# ThoraxSensor3_0.net
KiCad netlist of a schematic drawn in EAGLE
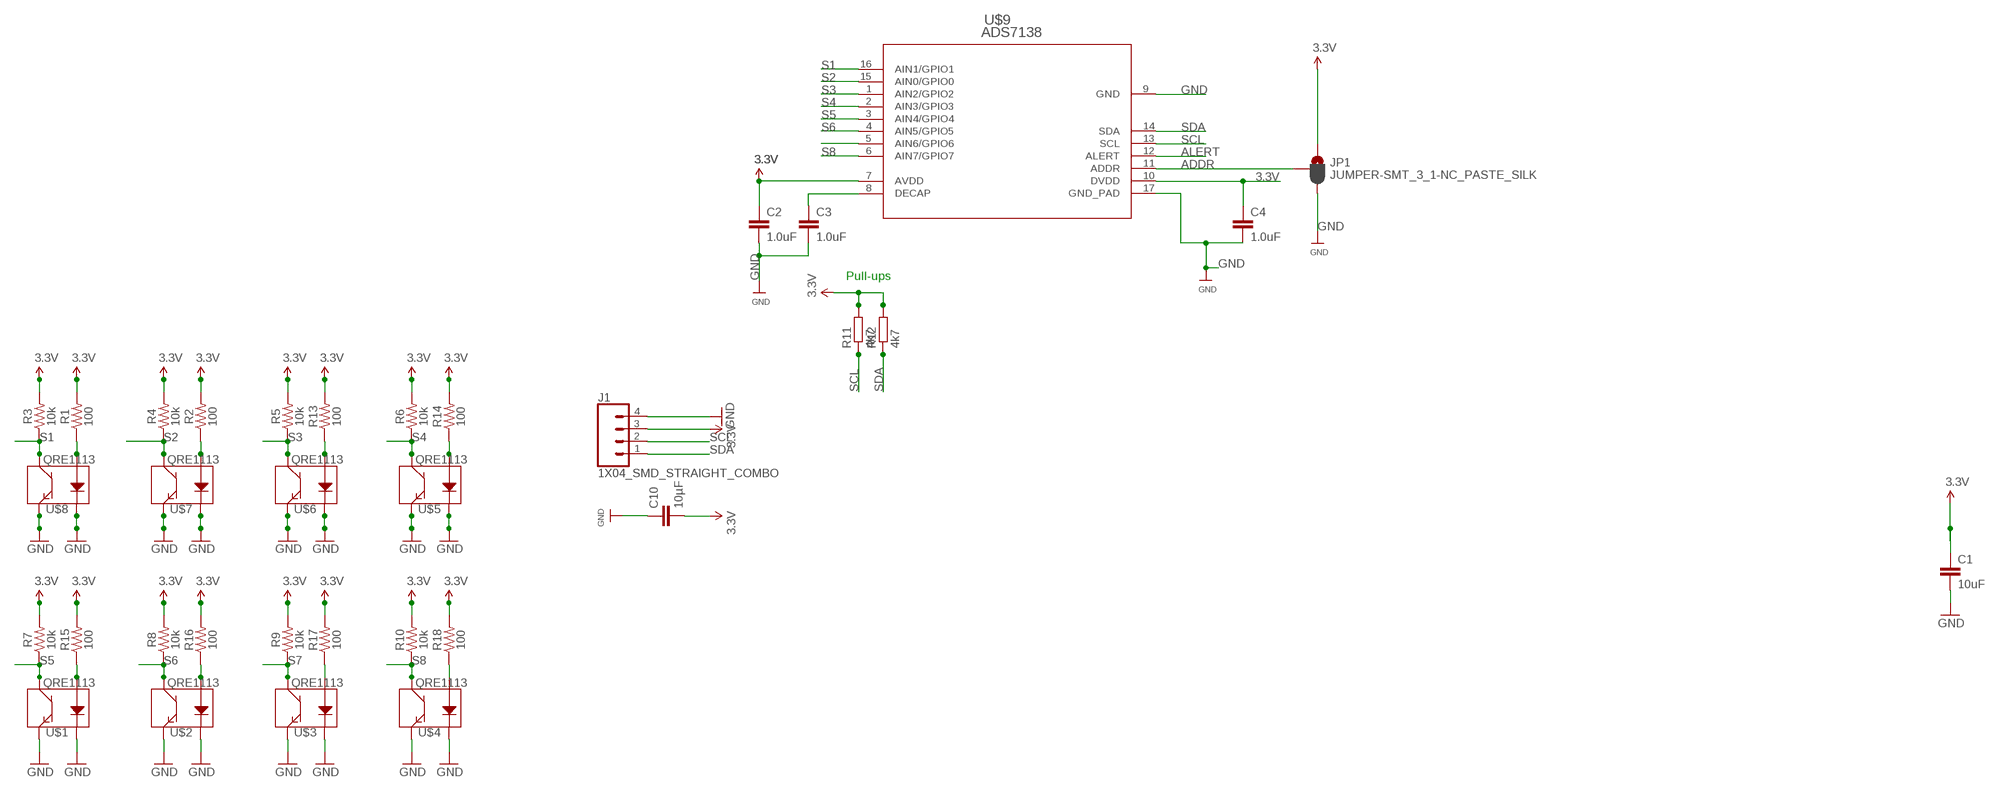
[diagram p0: schematic, sheet 1]

(export (version "E")
  (design (tool "Eeschema 10.0.6"))
  (components
    (comp (ref "C1")
      (value "10uF")
      (footprint "eagle-import:0805")
      (libsource (lib "eagle-import") (part "10UF-0805-10V-10%"))
    )
    (comp (ref "C2")
      (value "1.0uF")
      (footprint "eagle-import:0603")
      (libsource (lib "eagle-import") (part "1.0UF-0603-16V-10%"))
    )
    (comp (ref "C3")
      (value "1.0uF")
      (footprint "eagle-import:0603")
      (libsource (lib "eagle-import") (part "1.0UF-0603-16V-10%"))
    )
    (comp (ref "C4")
      (value "1.0uF")
      (footprint "eagle-import:0603")
      (libsource (lib "eagle-import") (part "1.0UF-0603-16V-10%"))
    )
    (comp (ref "C10")
      (value "10µF")
      (footprint "eagle-import:C0805")
      (libsource (lib "eagle-import") (part "C-EUC0805"))
    )
    (comp (ref "J1")
      (value "1X04_SMD_STRAIGHT_COMBO")
      (footprint "eagle-import:1X04_SMD_VERTICAL_COMBO")
      (libsource (lib "eagle-import") (part "CONN_04SMD_STRAIGHT_COMBO"))
    )
    (comp (ref "JP1")
      (value "JUMPER-SMT_3_1-NC_PASTE_SILK")
      (footprint "eagle-import:SMT-JUMPER_3_1-NC_PASTE_SILK")
      (libsource (lib "eagle-import") (part "JUMPER-SMT_3_1-NC_PASTE_SILK"))
    )
    (comp (ref "R1")
      (value "100")
      (footprint "eagle-import:0603")
      (libsource (lib "eagle-import") (part "100OHM-0603-1/4W-5%"))
    )
    (comp (ref "R2")
      (value "100")
      (footprint "eagle-import:0603")
      (libsource (lib "eagle-import") (part "100OHM-0603-1/4W-5%"))
    )
    (comp (ref "R3")
      (value "10k")
      (footprint "eagle-import:0603")
      (libsource (lib "eagle-import") (part "10KOHM-0603-1/10W-1%"))
    )
    (comp (ref "R4")
      (value "10k")
      (footprint "eagle-import:0603")
      (libsource (lib "eagle-import") (part "10KOHM-0603-1/10W-1%"))
    )
    (comp (ref "R5")
      (value "10k")
      (footprint "eagle-import:0603")
      (libsource (lib "eagle-import") (part "10KOHM-0603-1/10W-1%"))
    )
    (comp (ref "R6")
      (value "10k")
      (footprint "eagle-import:0603")
      (libsource (lib "eagle-import") (part "10KOHM-0603-1/10W-1%"))
    )
    (comp (ref "R7")
      (value "10k")
      (footprint "eagle-import:0603")
      (libsource (lib "eagle-import") (part "10KOHM-0603-1/10W-1%"))
    )
    (comp (ref "R8")
      (value "10k")
      (footprint "eagle-import:0603")
      (libsource (lib "eagle-import") (part "10KOHM-0603-1/10W-1%"))
    )
    (comp (ref "R9")
      (value "10k")
      (footprint "eagle-import:0603")
      (libsource (lib "eagle-import") (part "10KOHM-0603-1/10W-1%"))
    )
    (comp (ref "R10")
      (value "10k")
      (footprint "eagle-import:0603")
      (libsource (lib "eagle-import") (part "10KOHM-0603-1/10W-1%"))
    )
    (comp (ref "R11")
      (value "4k7")
      (footprint "eagle-import:R0603")
      (libsource (lib "eagle-import") (part "R-EU_R0603"))
    )
    (comp (ref "R12")
      (value "4k7")
      (footprint "eagle-import:R0603")
      (libsource (lib "eagle-import") (part "R-EU_R0603"))
    )
    (comp (ref "R13")
      (value "100")
      (footprint "eagle-import:0603")
      (libsource (lib "eagle-import") (part "100OHM-0603-1/4W-5%"))
    )
    (comp (ref "R14")
      (value "100")
      (footprint "eagle-import:0603")
      (libsource (lib "eagle-import") (part "100OHM-0603-1/4W-5%"))
    )
    (comp (ref "R15")
      (value "100")
      (footprint "eagle-import:0603")
      (libsource (lib "eagle-import") (part "100OHM-0603-1/4W-5%"))
    )
    (comp (ref "R16")
      (value "100")
      (footprint "eagle-import:0603")
      (libsource (lib "eagle-import") (part "100OHM-0603-1/4W-5%"))
    )
    (comp (ref "R17")
      (value "100")
      (footprint "eagle-import:0603")
      (libsource (lib "eagle-import") (part "100OHM-0603-1/4W-5%"))
    )
    (comp (ref "R18")
      (value "100")
      (footprint "eagle-import:0603")
      (libsource (lib "eagle-import") (part "100OHM-0603-1/4W-5%"))
    )
    (comp (ref "U$1")
      (value "QRE1113")
      (footprint "eagle-import:QRE1113")
      (libsource (lib "eagle-import") (part "QRE1113"))
    )
    (comp (ref "U$2")
      (value "QRE1113")
      (footprint "eagle-import:QRE1113")
      (libsource (lib "eagle-import") (part "QRE1113"))
    )
    (comp (ref "U$3")
      (value "QRE1113")
      (footprint "eagle-import:QRE1113")
      (libsource (lib "eagle-import") (part "QRE1113"))
    )
    (comp (ref "U$4")
      (value "QRE1113")
      (footprint "eagle-import:QRE1113")
      (libsource (lib "eagle-import") (part "QRE1113"))
    )
    (comp (ref "U$5")
      (value "QRE1113")
      (footprint "eagle-import:QRE1113")
      (libsource (lib "eagle-import") (part "QRE1113"))
    )
    (comp (ref "U$6")
      (value "QRE1113")
      (footprint "eagle-import:QRE1113")
      (libsource (lib "eagle-import") (part "QRE1113"))
    )
    (comp (ref "U$7")
      (value "QRE1113")
      (footprint "eagle-import:QRE1113")
      (libsource (lib "eagle-import") (part "QRE1113"))
    )
    (comp (ref "U$8")
      (value "QRE1113")
      (footprint "eagle-import:QRE1113")
      (libsource (lib "eagle-import") (part "QRE1113"))
    )
    (comp (ref "U$9")
      (value "ADS7138")
      (footprint "eagle-import:QFN_8IRTER_TEX")
      (libsource (lib "eagle-import") (part "ADS7138"))
    )
  )
  (nets
    (net (code "1") (name "/ADDR") (class "Default")
      (node (ref "JP1") (pin "2") (pinfunction "2_2") (pintype "passive"))
      (node (ref "U$9") (pin "11") (pinfunction "ADDR_11") (pintype "passive"))
    )
    (net (code "2") (name "/ALERT") (class "Default")
      (node (ref "U$9") (pin "12") (pinfunction "ALERT_12") (pintype "passive"))
    )
    (net (code "3") (name "/S1") (class "Default")
      (node (ref "R3") (pin "1") (pinfunction "1_1") (pintype "passive"))
      (node (ref "U$8") (pin "3") (pinfunction "C_3") (pintype "bidirectional"))
      (node (ref "U$9") (pin "16") (pinfunction "AIN1/GPIO1_16") (pintype "passive"))
    )
    (net (code "4") (name "/S2") (class "Default")
      (node (ref "R4") (pin "1") (pinfunction "1_1") (pintype "passive"))
      (node (ref "U$7") (pin "3") (pinfunction "C_3") (pintype "bidirectional"))
      (node (ref "U$9") (pin "15") (pinfunction "AIN0/GPIO0_15") (pintype "passive"))
    )
    (net (code "5") (name "/S3") (class "Default")
      (node (ref "R5") (pin "1") (pinfunction "1_1") (pintype "passive"))
      (node (ref "U$6") (pin "3") (pinfunction "C_3") (pintype "bidirectional"))
      (node (ref "U$9") (pin "1") (pinfunction "AIN2/GPIO2_1") (pintype "passive"))
    )
    (net (code "6") (name "/S4") (class "Default")
      (node (ref "R6") (pin "1") (pinfunction "1_1") (pintype "passive"))
      (node (ref "U$5") (pin "3") (pinfunction "C_3") (pintype "bidirectional"))
      (node (ref "U$9") (pin "2") (pinfunction "AIN3/GPIO3_2") (pintype "passive"))
    )
    (net (code "7") (name "/S5") (class "Default")
      (node (ref "R7") (pin "1") (pinfunction "1_1") (pintype "passive"))
      (node (ref "U$1") (pin "3") (pinfunction "C_3") (pintype "bidirectional"))
      (node (ref "U$9") (pin "3") (pinfunction "AIN4/GPIO4_3") (pintype "passive"))
    )
    (net (code "8") (name "/S6") (class "Default")
      (node (ref "R8") (pin "1") (pinfunction "1_1") (pintype "passive"))
      (node (ref "U$2") (pin "3") (pinfunction "C_3") (pintype "bidirectional"))
      (node (ref "U$9") (pin "4") (pinfunction "AIN5/GPIO5_4") (pintype "passive"))
    )
    (net (code "9") (name "/S7") (class "Default")
      (node (ref "R9") (pin "1") (pinfunction "1_1") (pintype "passive"))
      (node (ref "U$3") (pin "3") (pinfunction "C_3") (pintype "bidirectional"))
      (node (ref "U$9") (pin "5") (pinfunction "AIN6/GPIO6_5") (pintype "passive"))
    )
    (net (code "10") (name "/S8") (class "Default")
      (node (ref "R10") (pin "1") (pinfunction "1_1") (pintype "passive"))
      (node (ref "U$4") (pin "3") (pinfunction "C_3") (pintype "bidirectional"))
      (node (ref "U$9") (pin "6") (pinfunction "AIN7/GPIO7_6") (pintype "passive"))
    )
    (net (code "11") (name "/SCL") (class "Default")
      (node (ref "J1") (pin "2") (pinfunction "2_2") (pintype "passive"))
      (node (ref "R11") (pin "1") (pinfunction "1_1") (pintype "passive"))
      (node (ref "U$9") (pin "13") (pinfunction "SCL_13") (pintype "passive"))
    )
    (net (code "12") (name "/SDA") (class "Default")
      (node (ref "J1") (pin "1") (pinfunction "1_1") (pintype "passive"))
      (node (ref "R12") (pin "1") (pinfunction "1_1") (pintype "passive"))
      (node (ref "U$9") (pin "14") (pinfunction "SDA_14") (pintype "passive"))
    )
    (net (code "13") (name "3.3V") (class "Default")
      (node (ref "C1") (pin "1") (pinfunction "1_1") (pintype "passive"))
      (node (ref "C10") (pin "2") (pinfunction "2_2") (pintype "passive"))
      (node (ref "C2") (pin "1") (pinfunction "1_1") (pintype "passive"))
      (node (ref "C4") (pin "1") (pinfunction "1_1") (pintype "passive"))
      (node (ref "J1") (pin "3") (pinfunction "3_3") (pintype "passive"))
      (node (ref "JP1") (pin "1") (pinfunction "1_1") (pintype "passive"))
      (node (ref "R1") (pin "2") (pinfunction "2_2") (pintype "passive"))
      (node (ref "R10") (pin "2") (pinfunction "2_2") (pintype "passive"))
      (node (ref "R11") (pin "2") (pinfunction "2_2") (pintype "passive"))
      (node (ref "R12") (pin "2") (pinfunction "2_2") (pintype "passive"))
      (node (ref "R13") (pin "2") (pinfunction "2_2") (pintype "passive"))
      (node (ref "R14") (pin "2") (pinfunction "2_2") (pintype "passive"))
      (node (ref "R15") (pin "2") (pinfunction "2_2") (pintype "passive"))
      (node (ref "R16") (pin "2") (pinfunction "2_2") (pintype "passive"))
      (node (ref "R17") (pin "2") (pinfunction "2_2") (pintype "passive"))
      (node (ref "R18") (pin "2") (pinfunction "2_2") (pintype "passive"))
      (node (ref "R2") (pin "2") (pinfunction "2_2") (pintype "passive"))
      (node (ref "R3") (pin "2") (pinfunction "2_2") (pintype "passive"))
      (node (ref "R4") (pin "2") (pinfunction "2_2") (pintype "passive"))
      (node (ref "R5") (pin "2") (pinfunction "2_2") (pintype "passive"))
      (node (ref "R6") (pin "2") (pinfunction "2_2") (pintype "passive"))
      (node (ref "R7") (pin "2") (pinfunction "2_2") (pintype "passive"))
      (node (ref "R8") (pin "2") (pinfunction "2_2") (pintype "passive"))
      (node (ref "R9") (pin "2") (pinfunction "2_2") (pintype "passive"))
      (node (ref "U$9") (pin "10") (pinfunction "DVDD_10") (pintype "passive"))
      (node (ref "U$9") (pin "7") (pinfunction "AVDD_7") (pintype "passive"))
    )
    (net (code "14") (name "GND") (class "Default")
      (node (ref "C1") (pin "2") (pinfunction "2_2") (pintype "passive"))
      (node (ref "C10") (pin "1") (pinfunction "1_1") (pintype "passive"))
      (node (ref "C2") (pin "2") (pinfunction "2_2") (pintype "passive"))
      (node (ref "C3") (pin "2") (pinfunction "2_2") (pintype "passive"))
      (node (ref "C4") (pin "2") (pinfunction "2_2") (pintype "passive"))
      (node (ref "J1") (pin "4") (pinfunction "4_4") (pintype "passive"))
      (node (ref "JP1") (pin "3") (pinfunction "3_3") (pintype "passive"))
      (node (ref "U$1") (pin "2") (pinfunction "K_2") (pintype "bidirectional"))
      (node (ref "U$1") (pin "4") (pinfunction "E_4") (pintype "bidirectional"))
      (node (ref "U$2") (pin "2") (pinfunction "K_2") (pintype "bidirectional"))
      (node (ref "U$2") (pin "4") (pinfunction "E_4") (pintype "bidirectional"))
      (node (ref "U$3") (pin "2") (pinfunction "K_2") (pintype "bidirectional"))
      (node (ref "U$3") (pin "4") (pinfunction "E_4") (pintype "bidirectional"))
      (node (ref "U$4") (pin "2") (pinfunction "K_2") (pintype "bidirectional"))
      (node (ref "U$4") (pin "4") (pinfunction "E_4") (pintype "bidirectional"))
      (node (ref "U$5") (pin "2") (pinfunction "K_2") (pintype "bidirectional"))
      (node (ref "U$5") (pin "4") (pinfunction "E_4") (pintype "bidirectional"))
      (node (ref "U$6") (pin "2") (pinfunction "K_2") (pintype "bidirectional"))
      (node (ref "U$6") (pin "4") (pinfunction "E_4") (pintype "bidirectional"))
      (node (ref "U$7") (pin "2") (pinfunction "K_2") (pintype "bidirectional"))
      (node (ref "U$7") (pin "4") (pinfunction "E_4") (pintype "bidirectional"))
      (node (ref "U$8") (pin "2") (pinfunction "K_2") (pintype "bidirectional"))
      (node (ref "U$8") (pin "4") (pinfunction "E_4") (pintype "bidirectional"))
      (node (ref "U$9") (pin "17") (pinfunction "GND_PAD_17") (pintype "passive"))
      (node (ref "U$9") (pin "9") (pinfunction "GND_9") (pintype "passive"))
    )
    (net (code "15") (name "Net-(U$1-A)") (class "Default")
      (node (ref "R15") (pin "1") (pinfunction "1_1") (pintype "passive"))
      (node (ref "U$1") (pin "1") (pinfunction "A_1") (pintype "bidirectional"))
    )
    (net (code "16") (name "Net-(U$2-A)") (class "Default")
      (node (ref "R16") (pin "1") (pinfunction "1_1") (pintype "passive"))
      (node (ref "U$2") (pin "1") (pinfunction "A_1") (pintype "bidirectional"))
    )
    (net (code "17") (name "Net-(U$3-A)") (class "Default")
      (node (ref "R17") (pin "1") (pinfunction "1_1") (pintype "passive"))
      (node (ref "U$3") (pin "1") (pinfunction "A_1") (pintype "bidirectional"))
    )
    (net (code "18") (name "Net-(U$4-A)") (class "Default")
      (node (ref "R18") (pin "1") (pinfunction "1_1") (pintype "passive"))
      (node (ref "U$4") (pin "1") (pinfunction "A_1") (pintype "bidirectional"))
    )
    (net (code "19") (name "Net-(U$5-A)") (class "Default")
      (node (ref "R14") (pin "1") (pinfunction "1_1") (pintype "passive"))
      (node (ref "U$5") (pin "1") (pinfunction "A_1") (pintype "bidirectional"))
    )
    (net (code "20") (name "Net-(U$6-A)") (class "Default")
      (node (ref "R13") (pin "1") (pinfunction "1_1") (pintype "passive"))
      (node (ref "U$6") (pin "1") (pinfunction "A_1") (pintype "bidirectional"))
    )
    (net (code "21") (name "Net-(U$7-A)") (class "Default")
      (node (ref "R2") (pin "1") (pinfunction "1_1") (pintype "passive"))
      (node (ref "U$7") (pin "1") (pinfunction "A_1") (pintype "bidirectional"))
    )
    (net (code "22") (name "Net-(U$8-A)") (class "Default")
      (node (ref "R1") (pin "1") (pinfunction "1_1") (pintype "passive"))
      (node (ref "U$8") (pin "1") (pinfunction "A_1") (pintype "bidirectional"))
    )
    (net (code "23") (name "Net-(U$9-DECAP)") (class "Default")
      (node (ref "C3") (pin "1") (pinfunction "1_1") (pintype "passive"))
      (node (ref "U$9") (pin "8") (pinfunction "DECAP_8") (pintype "passive"))
    )
  )
)
